# lyre_eye_stocks_40mm_breakout.net
KiCad netlist of a schematic drawn in EAGLE
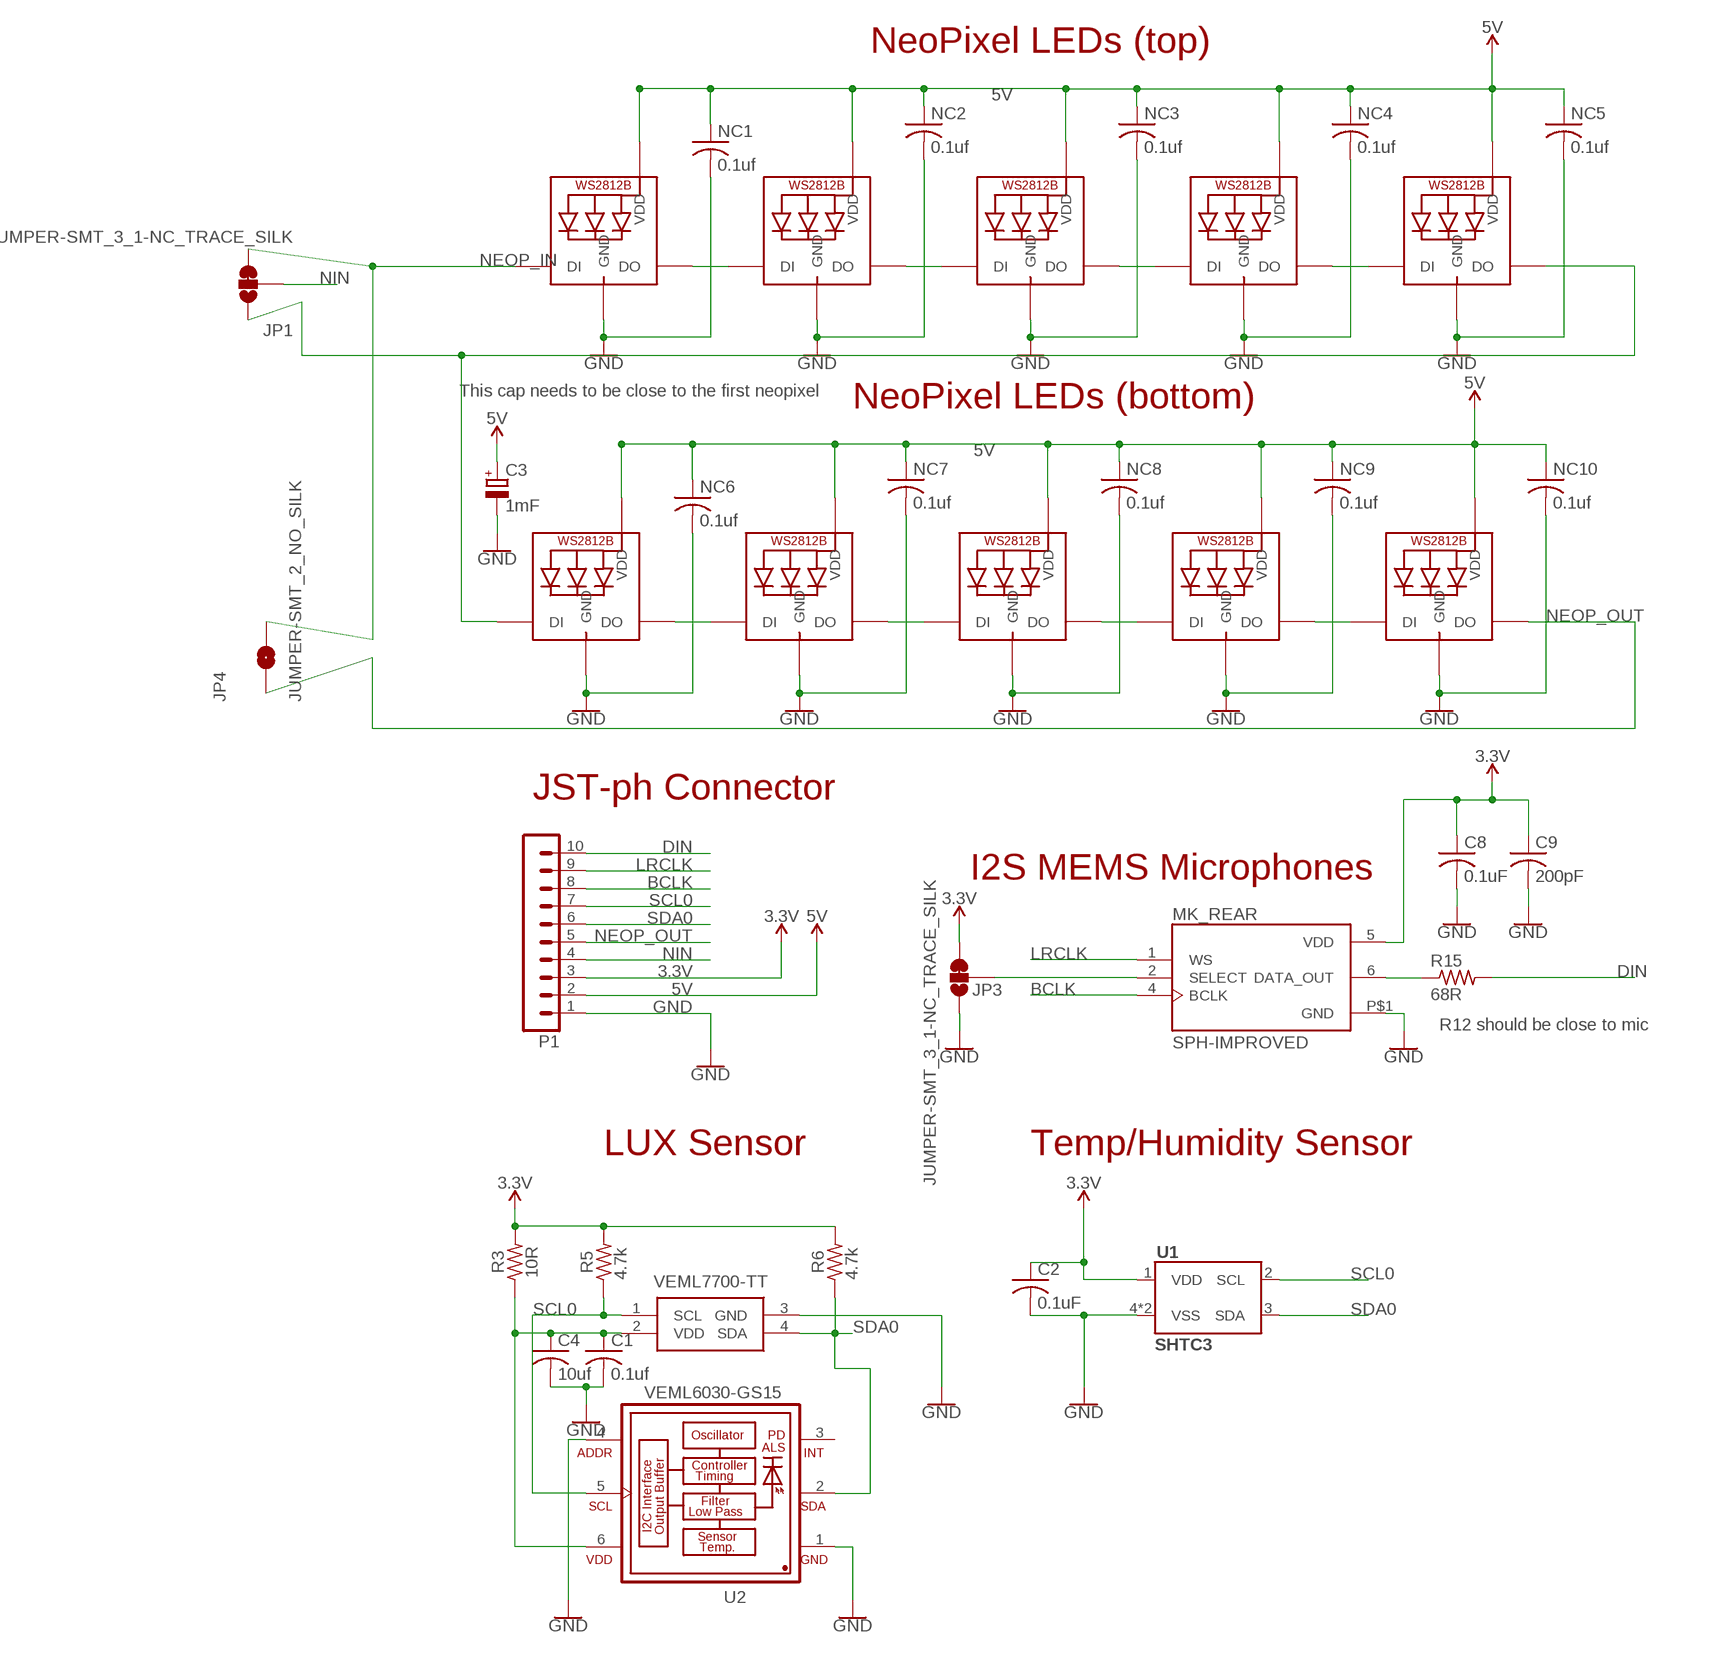
[diagram p0: schematic, sheet 1]

(export (version "E")
  (design (tool "Eeschema 10.0.6"))
  (components
    (comp (ref "C1")
      (value "0.1uf")
      (footprint "eagle-import:C0805")
      (libsource (lib "eagle-import") (part "C-USC0805"))
    )
    (comp (ref "C2")
      (value "0.1uF")
      (footprint "eagle-import:C0805")
      (libsource (lib "eagle-import") (part "C-USC0805"))
    )
    (comp (ref "C3")
      (value "1mF")
      (footprint "eagle-import:153CLV-1012")
      (libsource (lib "eagle-import") (part "CPOL-EU153CLV-1012"))
    )
    (comp (ref "C4")
      (value "10uf")
      (footprint "eagle-import:C0805")
      (libsource (lib "eagle-import") (part "C-USC0805"))
    )
    (comp (ref "C8")
      (value "0.1uF")
      (footprint "eagle-import:C0805")
      (libsource (lib "eagle-import") (part "C-USC0805"))
    )
    (comp (ref "C9")
      (value "200pF")
      (footprint "eagle-import:C0805")
      (libsource (lib "eagle-import") (part "C-USC0805"))
    )
    (comp (ref "JP1")
      (value "JUMPER-SMT_3_1-NC_TRACE_SILK")
      (footprint "eagle-import:SMT-JUMPER_3_1-NC_TRACE_SILK")
      (libsource (lib "eagle-import") (part "JUMPER-SMT_3_1-NC_TRACE_SILK"))
    )
    (comp (ref "JP3")
      (value "JUMPER-SMT_3_1-NC_TRACE_SILK")
      (footprint "eagle-import:SMT-JUMPER_3_1-NC_TRACE_SILK")
      (libsource (lib "eagle-import") (part "JUMPER-SMT_3_1-NC_TRACE_SILK"))
    )
    (comp (ref "JP4")
      (value "JUMPER-SMT_2_NO_SILK")
      (footprint "eagle-import:SMT-JUMPER_2_NO_SILK")
      (libsource (lib "eagle-import") (part "JUMPER-SMT_2_NO_SILK"))
    )
    (comp (ref "MK_REAR")
      (value "SPH-IMPROVED")
      (footprint "eagle-import:MIC_SPH0645LM4H-B_LARGER_RING")
      (libsource (lib "eagle-import") (part "SPH-IMPROVED"))
    )
    (comp (ref "NC1")
      (value "0.1uf")
      (footprint "eagle-import:C0805")
      (libsource (lib "eagle-import") (part "C-USC0805"))
    )
    (comp (ref "NC2")
      (value "0.1uf")
      (footprint "eagle-import:C0805")
      (libsource (lib "eagle-import") (part "C-USC0805"))
    )
    (comp (ref "NC3")
      (value "0.1uf")
      (footprint "eagle-import:C0805")
      (libsource (lib "eagle-import") (part "C-USC0805"))
    )
    (comp (ref "NC4")
      (value "0.1uf")
      (footprint "eagle-import:C0805")
      (libsource (lib "eagle-import") (part "C-USC0805"))
    )
    (comp (ref "NC5")
      (value "0.1uf")
      (footprint "eagle-import:C0805")
      (libsource (lib "eagle-import") (part "C-USC0805"))
    )
    (comp (ref "NC6")
      (value "0.1uf")
      (footprint "eagle-import:C0805")
      (libsource (lib "eagle-import") (part "C-USC0805"))
    )
    (comp (ref "NC7")
      (value "0.1uf")
      (footprint "eagle-import:C0805")
      (libsource (lib "eagle-import") (part "C-USC0805"))
    )
    (comp (ref "NC8")
      (value "0.1uf")
      (footprint "eagle-import:C0805")
      (libsource (lib "eagle-import") (part "C-USC0805"))
    )
    (comp (ref "NC9")
      (value "0.1uf")
      (footprint "eagle-import:C0805")
      (libsource (lib "eagle-import") (part "C-USC0805"))
    )
    (comp (ref "NC10")
      (value "0.1uf")
      (footprint "eagle-import:C0805")
      (libsource (lib "eagle-import") (part "C-USC0805"))
    )
    (comp (ref "NEO_01")
      (value "WS2812")
      (footprint "eagle-import:WS2812B")
      (libsource (lib "eagle-import") (part "WS2812"))
    )
    (comp (ref "NEO_02")
      (value "WS2812")
      (footprint "eagle-import:WS2812B")
      (libsource (lib "eagle-import") (part "WS2812"))
    )
    (comp (ref "NEO_03")
      (value "WS2812")
      (footprint "eagle-import:WS2812B")
      (libsource (lib "eagle-import") (part "WS2812"))
    )
    (comp (ref "NEO_04")
      (value "WS2812")
      (footprint "eagle-import:WS2812B")
      (libsource (lib "eagle-import") (part "WS2812"))
    )
    (comp (ref "NEO_05")
      (value "WS2812")
      (footprint "eagle-import:WS2812B")
      (libsource (lib "eagle-import") (part "WS2812"))
    )
    (comp (ref "NEO_06")
      (value "WS2812")
      (footprint "eagle-import:WS2812B")
      (libsource (lib "eagle-import") (part "WS2812"))
    )
    (comp (ref "NEO_07")
      (value "WS2812")
      (footprint "eagle-import:WS2812B")
      (libsource (lib "eagle-import") (part "WS2812"))
    )
    (comp (ref "NEO_08")
      (value "WS2812")
      (footprint "eagle-import:WS2812B")
      (libsource (lib "eagle-import") (part "WS2812"))
    )
    (comp (ref "NEO_09")
      (value "WS2812")
      (footprint "eagle-import:WS2812B")
      (libsource (lib "eagle-import") (part "WS2812"))
    )
    (comp (ref "NEO_10")
      (value "WS2812")
      (footprint "eagle-import:WS2812B")
      (libsource (lib "eagle-import") (part "WS2812"))
    )
    (comp (ref "P1")
      (value "B10B-PH-K")
      (footprint "eagle-import:B10B-PH-K")
      (libsource (lib "eagle-import") (part "B10B-PH-K"))
    )
    (comp (ref "R3")
      (value "10R")
      (footprint "eagle-import:R0805")
      (libsource (lib "eagle-import") (part "R-US_R0805"))
    )
    (comp (ref "R5")
      (value "4.7k")
      (footprint "eagle-import:R0805")
      (libsource (lib "eagle-import") (part "R-US_R0805"))
    )
    (comp (ref "R6")
      (value "4.7k")
      (footprint "eagle-import:R0805")
      (libsource (lib "eagle-import") (part "R-US_R0805"))
    )
    (comp (ref "R15")
      (value "68R")
      (footprint "eagle-import:R0805")
      (libsource (lib "eagle-import") (part "R-US_R0805"))
    )
    (comp (ref "U1")
      (value "SHTC3")
      (footprint "eagle-import:SHTC3")
      (libsource (lib "eagle-import") (part "SHTC3"))
    )
    (comp (ref "U2")
      (value "VEML6030-GS15")
      (footprint "eagle-import:VISHAY_VEML6030_2X2X0.87")
      (fields (field (name "MF") "Vishay Semiconductor"))
      (libsource (lib "eagle-import") (part "VEML6030-GS15"))
    )
    (comp (ref "VEML_F")
      (value "VEML7700-TT")
      (footprint "eagle-import:VEML7700")
      (fields (field (name "MOUSER_PART_NUMBER") "78-VEML7700-TT") (field (name "RS_PART_NUMBER") "1226791P"))
      (libsource (lib "eagle-import") (part "VEML7700-TT"))
    )
  )
  (nets
    (net (code "1") (name "/BCLK") (class "Default")
      (node (ref "MK_REAR") (pin "4") (pinfunction "BCLK_4") (pintype "input"))
      (node (ref "P1") (pin "8") (pinfunction "8_8") (pintype "passive"))
    )
    (net (code "2") (name "/DIN") (class "Default")
      (node (ref "P1") (pin "10") (pinfunction "10_10") (pintype "passive"))
      (node (ref "R15") (pin "2") (pinfunction "2_2") (pintype "passive"))
    )
    (net (code "3") (name "/LRCLK") (class "Default")
      (node (ref "MK_REAR") (pin "1") (pinfunction "WS_1") (pintype "input"))
      (node (ref "P1") (pin "9") (pinfunction "9_9") (pintype "passive"))
    )
    (net (code "4") (name "/NEOP_IN") (class "Default")
      (node (ref "JP1") (pin "3") (pinfunction "3_3") (pintype "passive"))
      (node (ref "JP4") (pin "2") (pinfunction "2_2") (pintype "passive"))
      (node (ref "NEO_01") (pin "4-DIN") (pinfunction "DI_4-DIN") (pintype "input"))
    )
    (net (code "5") (name "/NEOP_OUT") (class "Default")
      (node (ref "JP4") (pin "1") (pinfunction "1_1") (pintype "passive"))
      (node (ref "NEO_10") (pin "2-DOUT") (pinfunction "DO_2-DOUT") (pintype "output"))
      (node (ref "P1") (pin "5") (pinfunction "5_5") (pintype "passive"))
    )
    (net (code "6") (name "/NIN") (class "Default")
      (node (ref "JP1") (pin "2") (pinfunction "2_2") (pintype "passive"))
      (node (ref "P1") (pin "4") (pinfunction "4_4") (pintype "passive"))
    )
    (net (code "7") (name "/SCL0") (class "Default")
      (node (ref "P1") (pin "7") (pinfunction "7_7") (pintype "passive"))
      (node (ref "R5") (pin "1") (pinfunction "1_1") (pintype "passive"))
      (node (ref "U1") (pin "2") (pinfunction "SCL_2") (pintype "bidirectional"))
      (node (ref "U2") (pin "5") (pinfunction "SCL_5") (pintype "input"))
      (node (ref "VEML_F") (pin "1") (pinfunction "SCL_1") (pintype "bidirectional"))
    )
    (net (code "8") (name "/SDA0") (class "Default")
      (node (ref "P1") (pin "6") (pinfunction "6_6") (pintype "passive"))
      (node (ref "R6") (pin "1") (pinfunction "1_1") (pintype "passive"))
      (node (ref "U1") (pin "3") (pinfunction "SDA_3") (pintype "bidirectional"))
      (node (ref "U2") (pin "2") (pinfunction "SDA_2") (pintype "bidirectional"))
      (node (ref "VEML_F") (pin "4") (pinfunction "SDA_4") (pintype "bidirectional"))
    )
    (net (code "9") (name "3.3V") (class "Default")
      (node (ref "C2") (pin "1") (pinfunction "1_1") (pintype "passive"))
      (node (ref "C8") (pin "1") (pinfunction "1_1") (pintype "passive"))
      (node (ref "C9") (pin "1") (pinfunction "1_1") (pintype "passive"))
      (node (ref "JP3") (pin "3") (pinfunction "3_3") (pintype "passive"))
      (node (ref "MK_REAR") (pin "5") (pinfunction "VDD_5") (pintype "power_in"))
      (node (ref "P1") (pin "3") (pinfunction "3_3") (pintype "passive"))
      (node (ref "R3") (pin "2") (pinfunction "2_2") (pintype "passive"))
      (node (ref "R5") (pin "2") (pinfunction "2_2") (pintype "passive"))
      (node (ref "R6") (pin "2") (pinfunction "2_2") (pintype "passive"))
      (node (ref "U1") (pin "1") (pinfunction "VDD_1") (pintype "bidirectional"))
    )
    (net (code "10") (name "5V") (class "Default")
      (node (ref "C3") (pin "+") (pinfunction "+_+") (pintype "passive"))
      (node (ref "NC1") (pin "1") (pinfunction "1_1") (pintype "passive"))
      (node (ref "NC10") (pin "1") (pinfunction "1_1") (pintype "passive"))
      (node (ref "NC2") (pin "1") (pinfunction "1_1") (pintype "passive"))
      (node (ref "NC3") (pin "1") (pinfunction "1_1") (pintype "passive"))
      (node (ref "NC4") (pin "1") (pinfunction "1_1") (pintype "passive"))
      (node (ref "NC5") (pin "1") (pinfunction "1_1") (pintype "passive"))
      (node (ref "NC6") (pin "1") (pinfunction "1_1") (pintype "passive"))
      (node (ref "NC7") (pin "1") (pinfunction "1_1") (pintype "passive"))
      (node (ref "NC8") (pin "1") (pinfunction "1_1") (pintype "passive"))
      (node (ref "NC9") (pin "1") (pinfunction "1_1") (pintype "passive"))
      (node (ref "NEO_01") (pin "1-VDD") (pinfunction "VDD_1-VDD") (pintype "power_in"))
      (node (ref "NEO_02") (pin "1-VDD") (pinfunction "VDD_1-VDD") (pintype "power_in"))
      (node (ref "NEO_03") (pin "1-VDD") (pinfunction "VDD_1-VDD") (pintype "power_in"))
      (node (ref "NEO_04") (pin "1-VDD") (pinfunction "VDD_1-VDD") (pintype "power_in"))
      (node (ref "NEO_05") (pin "1-VDD") (pinfunction "VDD_1-VDD") (pintype "power_in"))
      (node (ref "NEO_06") (pin "1-VDD") (pinfunction "VDD_1-VDD") (pintype "power_in"))
      (node (ref "NEO_07") (pin "1-VDD") (pinfunction "VDD_1-VDD") (pintype "power_in"))
      (node (ref "NEO_08") (pin "1-VDD") (pinfunction "VDD_1-VDD") (pintype "power_in"))
      (node (ref "NEO_09") (pin "1-VDD") (pinfunction "VDD_1-VDD") (pintype "power_in"))
      (node (ref "NEO_10") (pin "1-VDD") (pinfunction "VDD_1-VDD") (pintype "power_in"))
      (node (ref "P1") (pin "2") (pinfunction "2_2") (pintype "passive"))
    )
    (net (code "11") (name "GND") (class "Default")
      (node (ref "C1") (pin "2") (pinfunction "2_2") (pintype "passive"))
      (node (ref "C2") (pin "2") (pinfunction "2_2") (pintype "passive"))
      (node (ref "C3") (pin "-") (pinfunction "-_-") (pintype "passive"))
      (node (ref "C4") (pin "2") (pinfunction "2_2") (pintype "passive"))
      (node (ref "C8") (pin "2") (pinfunction "2_2") (pintype "passive"))
      (node (ref "C9") (pin "2") (pinfunction "2_2") (pintype "passive"))
      (node (ref "JP3") (pin "1") (pinfunction "1_1") (pintype "passive"))
      (node (ref "MK_REAR") (pin "P$1") (pinfunction "GND_P$1") (pintype "power_in"))
      (node (ref "NC1") (pin "2") (pinfunction "2_2") (pintype "passive"))
      (node (ref "NC10") (pin "2") (pinfunction "2_2") (pintype "passive"))
      (node (ref "NC2") (pin "2") (pinfunction "2_2") (pintype "passive"))
      (node (ref "NC3") (pin "2") (pinfunction "2_2") (pintype "passive"))
      (node (ref "NC4") (pin "2") (pinfunction "2_2") (pintype "passive"))
      (node (ref "NC5") (pin "2") (pinfunction "2_2") (pintype "passive"))
      (node (ref "NC6") (pin "2") (pinfunction "2_2") (pintype "passive"))
      (node (ref "NC7") (pin "2") (pinfunction "2_2") (pintype "passive"))
      (node (ref "NC8") (pin "2") (pinfunction "2_2") (pintype "passive"))
      (node (ref "NC9") (pin "2") (pinfunction "2_2") (pintype "passive"))
      (node (ref "NEO_01") (pin "3-GND") (pinfunction "GND_3-GND") (pintype "power_in"))
      (node (ref "NEO_02") (pin "3-GND") (pinfunction "GND_3-GND") (pintype "power_in"))
      (node (ref "NEO_03") (pin "3-GND") (pinfunction "GND_3-GND") (pintype "power_in"))
      (node (ref "NEO_04") (pin "3-GND") (pinfunction "GND_3-GND") (pintype "power_in"))
      (node (ref "NEO_05") (pin "3-GND") (pinfunction "GND_3-GND") (pintype "power_in"))
      (node (ref "NEO_06") (pin "3-GND") (pinfunction "GND_3-GND") (pintype "power_in"))
      (node (ref "NEO_07") (pin "3-GND") (pinfunction "GND_3-GND") (pintype "power_in"))
      (node (ref "NEO_08") (pin "3-GND") (pinfunction "GND_3-GND") (pintype "power_in"))
      (node (ref "NEO_09") (pin "3-GND") (pinfunction "GND_3-GND") (pintype "power_in"))
      (node (ref "NEO_10") (pin "3-GND") (pinfunction "GND_3-GND") (pintype "power_in"))
      (node (ref "P1") (pin "1") (pinfunction "1_1") (pintype "passive"))
      (node (ref "U1") (pin "4") (pinfunction "VSS_4") (pintype "bidirectional"))
      (node (ref "U1") (pin "5") (pinfunction "VSS_5") (pintype "bidirectional"))
      (node (ref "U2") (pin "1") (pinfunction "GND_1") (pintype "power_in"))
      (node (ref "U2") (pin "4") (pinfunction "ADDR_4") (pintype "bidirectional"))
      (node (ref "VEML_F") (pin "3") (pinfunction "GND_3") (pintype "bidirectional"))
    )
    (net (code "12") (name "Net-(MK_REAR-DATA_OUT)") (class "Default")
      (node (ref "MK_REAR") (pin "6") (pinfunction "DATA_OUT_6") (pintype "output"))
      (node (ref "R15") (pin "1") (pinfunction "1_1") (pintype "passive"))
    )
    (net (code "13") (name "Net-(MK_REAR-SELECT)") (class "Default")
      (node (ref "JP3") (pin "2") (pinfunction "2_2") (pintype "passive"))
      (node (ref "MK_REAR") (pin "2") (pinfunction "SELECT_2") (pintype "input"))
    )
    (net (code "14") (name "Net-(NEO_01-DO)") (class "Default")
      (node (ref "NEO_01") (pin "2-DOUT") (pinfunction "DO_2-DOUT") (pintype "output"))
      (node (ref "NEO_02") (pin "4-DIN") (pinfunction "DI_4-DIN") (pintype "input"))
    )
    (net (code "15") (name "Net-(NEO_02-DO)") (class "Default")
      (node (ref "NEO_02") (pin "2-DOUT") (pinfunction "DO_2-DOUT") (pintype "output"))
      (node (ref "NEO_03") (pin "4-DIN") (pinfunction "DI_4-DIN") (pintype "input"))
    )
    (net (code "16") (name "Net-(NEO_03-DO)") (class "Default")
      (node (ref "NEO_03") (pin "2-DOUT") (pinfunction "DO_2-DOUT") (pintype "output"))
      (node (ref "NEO_04") (pin "4-DIN") (pinfunction "DI_4-DIN") (pintype "input"))
    )
    (net (code "17") (name "Net-(NEO_04-DO)") (class "Default")
      (node (ref "NEO_04") (pin "2-DOUT") (pinfunction "DO_2-DOUT") (pintype "output"))
      (node (ref "NEO_05") (pin "4-DIN") (pinfunction "DI_4-DIN") (pintype "input"))
    )
    (net (code "18") (name "Net-(NEO_05-DO)") (class "Default")
      (node (ref "JP1") (pin "1") (pinfunction "1_1") (pintype "passive"))
      (node (ref "NEO_05") (pin "2-DOUT") (pinfunction "DO_2-DOUT") (pintype "output"))
      (node (ref "NEO_06") (pin "4-DIN") (pinfunction "DI_4-DIN") (pintype "input"))
    )
    (net (code "19") (name "Net-(NEO_06-DO)") (class "Default")
      (node (ref "NEO_06") (pin "2-DOUT") (pinfunction "DO_2-DOUT") (pintype "output"))
      (node (ref "NEO_07") (pin "4-DIN") (pinfunction "DI_4-DIN") (pintype "input"))
    )
    (net (code "20") (name "Net-(NEO_07-DO)") (class "Default")
      (node (ref "NEO_07") (pin "2-DOUT") (pinfunction "DO_2-DOUT") (pintype "output"))
      (node (ref "NEO_08") (pin "4-DIN") (pinfunction "DI_4-DIN") (pintype "input"))
    )
    (net (code "21") (name "Net-(NEO_08-DO)") (class "Default")
      (node (ref "NEO_08") (pin "2-DOUT") (pinfunction "DO_2-DOUT") (pintype "output"))
      (node (ref "NEO_09") (pin "4-DIN") (pinfunction "DI_4-DIN") (pintype "input"))
    )
    (net (code "22") (name "Net-(NEO_09-DO)") (class "Default")
      (node (ref "NEO_09") (pin "2-DOUT") (pinfunction "DO_2-DOUT") (pintype "output"))
      (node (ref "NEO_10") (pin "4-DIN") (pinfunction "DI_4-DIN") (pintype "input"))
    )
    (net (code "23") (name "Net-(U2-VDD)") (class "Default")
      (node (ref "C1") (pin "1") (pinfunction "1_1") (pintype "passive"))
      (node (ref "C4") (pin "1") (pinfunction "1_1") (pintype "passive"))
      (node (ref "R3") (pin "1") (pinfunction "1_1") (pintype "passive"))
      (node (ref "U2") (pin "6") (pinfunction "VDD_6") (pintype "power_in"))
      (node (ref "VEML_F") (pin "2") (pinfunction "VDD_2") (pintype "bidirectional"))
    )
    (net (code "24") (name "unconnected-(U2-INT-Pad3)") (class "Default")
      (node (ref "U2") (pin "3") (pinfunction "INT_3") (pintype "output"))
    )
  )
)
